# TIDA-010954-Control.net
KiCad netlist of a schematic drawn in Altium Designer
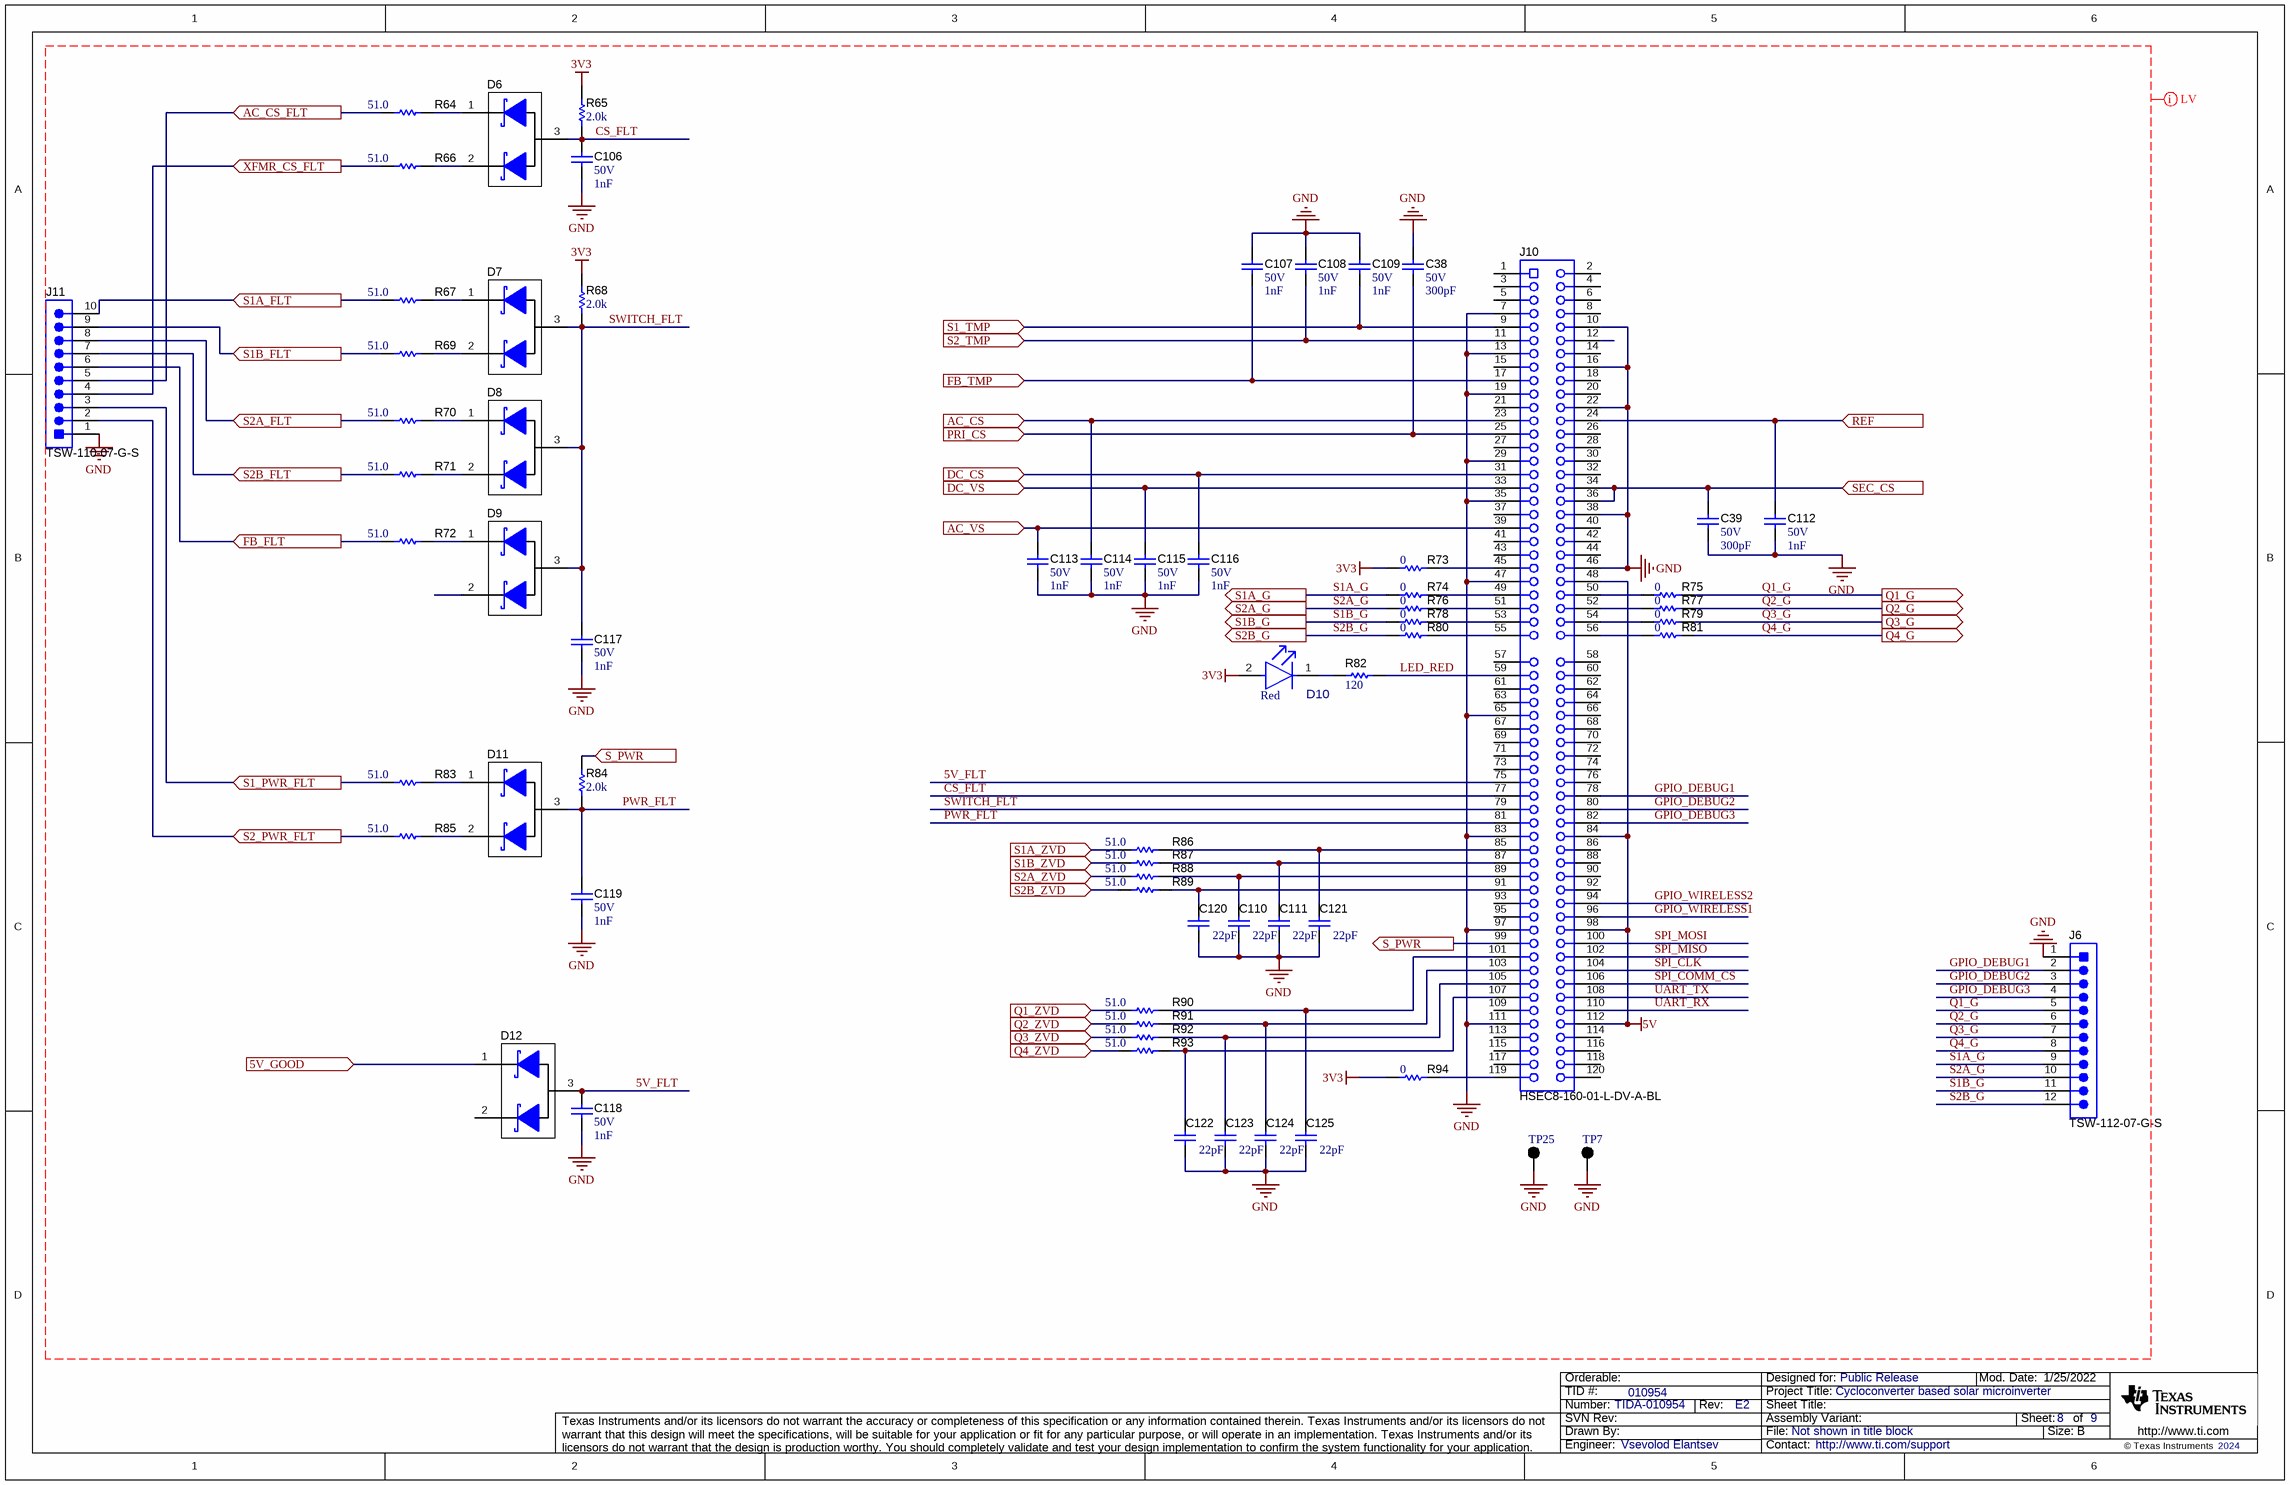
[diagram p0: TIDA-010954-Control.SchDoc]

(export (version "E")
  (design (tool "Eeschema 10.0.6"))
  (components
    (comp (ref "C38")
      (value "GRM1885C1H301JA01D")
      (footprint "0603")
      (description "CAP, CERM, 300 pF, 50 V, +/- 5%, C0G/NP0, 0603")
      (fields
        (field (name "MANUFACTURER") "MuRata")
        (field (name "VDC_V") "50V")
        (field (name "VALUEDISPLAYED") "300pF")
        (field (name "PUBLISHER") "Texas Instruments")
      )
      (libsource (lib "Altium Vault - TI") (part "Capacitor"))
    )
    (comp (ref "C39")
      (value "GRM1885C1H301JA01D")
      (footprint "0603")
      (description "CAP, CERM, 300 pF, 50 V, +/- 5%, C0G/NP0, 0603")
      (fields
        (field (name "MANUFACTURER") "MuRata")
        (field (name "VDC_V") "50V")
        (field (name "VALUEDISPLAYED") "300pF")
        (field (name "PUBLISHER") "Texas Instruments")
      )
      (libsource (lib "Altium Vault - TI") (part "Capacitor"))
    )
    (comp (ref "C106")
      (value "GRM1885C1H102JA01D")
      (footprint "0603")
      (description "CAP, CERM, 1000 pF, 50 V, +/- 5%, C0G/NP0, 0603")
      (fields
        (field (name "MANUFACTURER") "MuRata")
        (field (name "VDC_V") "50V")
        (field (name "VALUEDISPLAYED") "1nF")
        (field (name "PUBLISHER") "Texas Instruments")
      )
      (libsource (lib "Altium Vault - TI") (part "Capacitor"))
    )
    (comp (ref "C107")
      (value "GRM1885C1H102JA01D")
      (footprint "0603")
      (description "CAP, CERM, 1000 pF, 50 V, +/- 5%, C0G/NP0, 0603")
      (fields
        (field (name "MANUFACTURER") "MuRata")
        (field (name "VDC_V") "50V")
        (field (name "VALUEDISPLAYED") "1nF")
        (field (name "PUBLISHER") "Texas Instruments")
      )
      (libsource (lib "Altium Vault - TI") (part "Capacitor"))
    )
    (comp (ref "C108")
      (value "GRM1885C1H102JA01D")
      (footprint "0603")
      (description "CAP, CERM, 1000 pF, 50 V, +/- 5%, C0G/NP0, 0603")
      (fields
        (field (name "MANUFACTURER") "MuRata")
        (field (name "VDC_V") "50V")
        (field (name "VALUEDISPLAYED") "1nF")
        (field (name "PUBLISHER") "Texas Instruments")
      )
      (libsource (lib "Altium Vault - TI") (part "Capacitor"))
    )
    (comp (ref "C109")
      (value "GRM1885C1H102JA01D")
      (footprint "0603")
      (description "CAP, CERM, 1000 pF, 50 V, +/- 5%, C0G/NP0, 0603")
      (fields
        (field (name "MANUFACTURER") "MuRata")
        (field (name "VDC_V") "50V")
        (field (name "VALUEDISPLAYED") "1nF")
        (field (name "PUBLISHER") "Texas Instruments")
      )
      (libsource (lib "Altium Vault - TI") (part "Capacitor"))
    )
    (comp (ref "C110")
      (value "GRM1885C1H220JA01D")
      (footprint "0603")
      (description "CAP, CERM, 22 pF, 50 V, +/- 5%, C0G/NP0, 0603")
      (fields
        (field (name "MANUFACTURER") "MuRata")
        (field (name "VALUEDISPLAYED") "22pF")
        (field (name "PUBLISHER") "Texas Instruments")
      )
      (libsource (lib "Altium Vault - TI") (part "Capacitor"))
    )
    (comp (ref "C111")
      (value "GRM1885C1H220JA01D")
      (footprint "0603")
      (description "CAP, CERM, 22 pF, 50 V, +/- 5%, C0G/NP0, 0603")
      (fields
        (field (name "MANUFACTURER") "MuRata")
        (field (name "VALUEDISPLAYED") "22pF")
        (field (name "PUBLISHER") "Texas Instruments")
      )
      (libsource (lib "Altium Vault - TI") (part "Capacitor"))
    )
    (comp (ref "C112")
      (value "GRM1885C1H102JA01D")
      (footprint "0603")
      (description "CAP, CERM, 1000 pF, 50 V, +/- 5%, C0G/NP0, 0603")
      (fields
        (field (name "MANUFACTURER") "MuRata")
        (field (name "VDC_V") "50V")
        (field (name "VALUEDISPLAYED") "1nF")
        (field (name "PUBLISHER") "Texas Instruments")
      )
      (libsource (lib "Altium Vault - TI") (part "Capacitor"))
    )
    (comp (ref "C113")
      (value "GRM1885C1H102JA01D")
      (footprint "0603")
      (description "CAP, CERM, 1000 pF, 50 V, +/- 5%, C0G/NP0, 0603")
      (fields
        (field (name "MANUFACTURER") "MuRata")
        (field (name "VDC_V") "50V")
        (field (name "VALUEDISPLAYED") "1nF")
        (field (name "PUBLISHER") "Texas Instruments")
      )
      (libsource (lib "Altium Vault - TI") (part "Capacitor"))
    )
    (comp (ref "C114")
      (value "GRM1885C1H102JA01D")
      (footprint "0603")
      (description "CAP, CERM, 1000 pF, 50 V, +/- 5%, C0G/NP0, 0603")
      (fields
        (field (name "MANUFACTURER") "MuRata")
        (field (name "VDC_V") "50V")
        (field (name "VALUEDISPLAYED") "1nF")
        (field (name "PUBLISHER") "Texas Instruments")
      )
      (libsource (lib "Altium Vault - TI") (part "Capacitor"))
    )
    (comp (ref "C115")
      (value "GRM1885C1H102JA01D")
      (footprint "0603")
      (description "CAP, CERM, 1000 pF, 50 V, +/- 5%, C0G/NP0, 0603")
      (fields
        (field (name "MANUFACTURER") "MuRata")
        (field (name "VDC_V") "50V")
        (field (name "VALUEDISPLAYED") "1nF")
        (field (name "PUBLISHER") "Texas Instruments")
      )
      (libsource (lib "Altium Vault - TI") (part "Capacitor"))
    )
    (comp (ref "C116")
      (value "GRM1885C1H102JA01D")
      (footprint "0603")
      (description "CAP, CERM, 1000 pF, 50 V, +/- 5%, C0G/NP0, 0603")
      (fields
        (field (name "MANUFACTURER") "MuRata")
        (field (name "VDC_V") "50V")
        (field (name "VALUEDISPLAYED") "1nF")
        (field (name "PUBLISHER") "Texas Instruments")
      )
      (libsource (lib "Altium Vault - TI") (part "Capacitor"))
    )
    (comp (ref "C117")
      (value "GRM1885C1H102JA01D")
      (footprint "0603")
      (description "CAP, CERM, 1000 pF, 50 V, +/- 5%, C0G/NP0, 0603")
      (fields
        (field (name "MANUFACTURER") "MuRata")
        (field (name "VDC_V") "50V")
        (field (name "VALUEDISPLAYED") "1nF")
        (field (name "PUBLISHER") "Texas Instruments")
      )
      (libsource (lib "Altium Vault - TI") (part "Capacitor"))
    )
    (comp (ref "C118")
      (value "GRM1885C1H102JA01D")
      (footprint "0603")
      (description "CAP, CERM, 1000 pF, 50 V, +/- 5%, C0G/NP0, 0603")
      (fields
        (field (name "MANUFACTURER") "MuRata")
        (field (name "VDC_V") "50V")
        (field (name "VALUEDISPLAYED") "1nF")
        (field (name "PUBLISHER") "Texas Instruments")
      )
      (libsource (lib "Altium Vault - TI") (part "Capacitor"))
    )
    (comp (ref "C119")
      (value "GRM1885C1H102JA01D")
      (footprint "0603")
      (description "CAP, CERM, 1000 pF, 50 V, +/- 5%, C0G/NP0, 0603")
      (fields
        (field (name "MANUFACTURER") "MuRata")
        (field (name "VDC_V") "50V")
        (field (name "VALUEDISPLAYED") "1nF")
        (field (name "PUBLISHER") "Texas Instruments")
      )
      (libsource (lib "Altium Vault - TI") (part "Capacitor"))
    )
    (comp (ref "C120")
      (value "GRM1885C1H220JA01D")
      (footprint "0603")
      (description "CAP, CERM, 22 pF, 50 V, +/- 5%, C0G/NP0, 0603")
      (fields
        (field (name "MANUFACTURER") "MuRata")
        (field (name "VALUEDISPLAYED") "22pF")
        (field (name "PUBLISHER") "Texas Instruments")
      )
      (libsource (lib "Altium Vault - TI") (part "Capacitor"))
    )
    (comp (ref "C121")
      (value "GRM1885C1H220JA01D")
      (footprint "0603")
      (description "CAP, CERM, 22 pF, 50 V, +/- 5%, C0G/NP0, 0603")
      (fields
        (field (name "MANUFACTURER") "MuRata")
        (field (name "VALUEDISPLAYED") "22pF")
        (field (name "PUBLISHER") "Texas Instruments")
      )
      (libsource (lib "Altium Vault - TI") (part "Capacitor"))
    )
    (comp (ref "C122")
      (value "GRM1885C1H220JA01D")
      (footprint "0603")
      (description "CAP, CERM, 22 pF, 50 V, +/- 5%, C0G/NP0, 0603")
      (fields
        (field (name "MANUFACTURER") "MuRata")
        (field (name "VALUEDISPLAYED") "22pF")
        (field (name "PUBLISHER") "Texas Instruments")
      )
      (libsource (lib "Altium Vault - TI") (part "Capacitor"))
    )
    (comp (ref "C123")
      (value "GRM1885C1H220JA01D")
      (footprint "0603")
      (description "CAP, CERM, 22 pF, 50 V, +/- 5%, C0G/NP0, 0603")
      (fields
        (field (name "MANUFACTURER") "MuRata")
        (field (name "VALUEDISPLAYED") "22pF")
        (field (name "PUBLISHER") "Texas Instruments")
      )
      (libsource (lib "Altium Vault - TI") (part "Capacitor"))
    )
    (comp (ref "C124")
      (value "GRM1885C1H220JA01D")
      (footprint "0603")
      (description "CAP, CERM, 22 pF, 50 V, +/- 5%, C0G/NP0, 0603")
      (fields
        (field (name "MANUFACTURER") "MuRata")
        (field (name "VALUEDISPLAYED") "22pF")
        (field (name "PUBLISHER") "Texas Instruments")
      )
      (libsource (lib "Altium Vault - TI") (part "Capacitor"))
    )
    (comp (ref "C125")
      (value "GRM1885C1H220JA01D")
      (footprint "0603")
      (description "CAP, CERM, 22 pF, 50 V, +/- 5%, C0G/NP0, 0603")
      (fields
        (field (name "MANUFACTURER") "MuRata")
        (field (name "VALUEDISPLAYED") "22pF")
        (field (name "PUBLISHER") "Texas Instruments")
      )
      (libsource (lib "Altium Vault - TI") (part "Capacitor"))
    )
    (comp (ref "D6")
      (value "BAT54AWT-TP")
      (footprint "SOT-323")
      (description "Diode, Schottky, 30 V, 0.2 A, SOT-323")
      (fields (field (name "MANUFACTURER") "Micro Commercial Components"))
      (libsource (lib "Altium Vault - TI") (part "DIODE_SCHOTTKY_A3C1_A3C2"))
    )
    (comp (ref "D7")
      (value "BAT54AWT-TP")
      (footprint "SOT-323")
      (description "Diode, Schottky, 30 V, 0.2 A, SOT-323")
      (fields (field (name "MANUFACTURER") "Micro Commercial Components"))
      (libsource (lib "Altium Vault - TI") (part "DIODE_SCHOTTKY_A3C1_A3C2"))
    )
    (comp (ref "D8")
      (value "BAT54AWT-TP")
      (footprint "SOT-323")
      (description "Diode, Schottky, 30 V, 0.2 A, SOT-323")
      (fields (field (name "MANUFACTURER") "Micro Commercial Components"))
      (libsource (lib "Altium Vault - TI") (part "DIODE_SCHOTTKY_A3C1_A3C2"))
    )
    (comp (ref "D9")
      (value "BAT54AWT-TP")
      (footprint "SOT-323")
      (description "Diode, Schottky, 30 V, 0.2 A, SOT-323")
      (fields (field (name "MANUFACTURER") "Micro Commercial Components"))
      (libsource (lib "Altium Vault - TI") (part "DIODE_SCHOTTKY_A3C1_A3C2"))
    )
    (comp (ref "D10")
      (value "APG1608SURKC/T")
      (footprint "FP-APG1608SURKC_T_0603-MFG")
      (description "Red 630nm LED Indication - Discrete 2V 0603 (1608 Metric)")
      (fields
        (field (name "MANUFACTURER") "Kingbright")
        (field (name "MOUSER PART NUMBER") "604-APG1608SURKC/T")
        (field (name "COLOR") "Red")
      )
      (libsource (lib "Altium Vault - TI") (part "SYM-APG1608SURKC_T"))
    )
    (comp (ref "D11")
      (value "BAT54AWT-TP")
      (footprint "SOT-323")
      (description "Diode, Schottky, 30 V, 0.2 A, SOT-323")
      (fields (field (name "MANUFACTURER") "Micro Commercial Components"))
      (libsource (lib "Altium Vault - TI") (part "DIODE_SCHOTTKY_A3C1_A3C2"))
    )
    (comp (ref "D12")
      (value "BAT54AWT-TP")
      (footprint "SOT-323")
      (description "Diode, Schottky, 30 V, 0.2 A, SOT-323")
      (fields (field (name "MANUFACTURER") "Micro Commercial Components"))
      (libsource (lib "Altium Vault - TI") (part "DIODE_SCHOTTKY_A3C1_A3C2"))
    )
    (comp (ref "J6")
      (value "TSW-112-07-G-S")
      (footprint "TSW-112-07-G-S")
      (description "Header, 100mil, 12x1, Gold, TH")
      (fields (field (name "MANUFACTURER") "Samtec") (field (name "PUBLISHER") "Texas Instruments"))
      (libsource (lib "Altium Vault - TI") (part "Header_12x1"))
    )
    (comp (ref "J10")
      (value "HSEC8-160-01-L-DV-A-BL")
      (footprint "controlCARD-120HSEC")
      (description "C2000 controlCARD-120HSEC connector, SMT")
      (fields (field (name "MANUFACTURER") "Samtec"))
      (libsource (lib "Altium Vault - TI") (part "controlCARD-120HSEC"))
    )
    (comp (ref "J11")
      (value "TSW-110-07-G-S")
      (footprint "TSW-110-07-G-S")
      (description "Header, 100mil, 10x1, Gold, TH")
      (fields (field (name "MANUFACTURER") "Samtec") (field (name "PUBLISHER") "Texas Instruments"))
      (libsource (lib "Altium Vault - TI") (part "Header_10x1"))
    )
    (comp (ref "R64")
      (value "RC0603FR-0751RL")
      (footprint "0603")
      (description "RES, 51.0, 1%, 0.1 W, 0603")
      (fields (field (name "MANUFACTURER") "Yageo") (field (name "VALUEDISPLAYED") "51.0"))
      (libsource (lib "Altium Vault - TI") (part "Resistor"))
    )
    (comp (ref "R65")
      (value "RC0603JR-072KL")
      (footprint "0603")
      (description "RES, 2.0 k, 5%, 0.1 W, 0603")
      (fields (field (name "MANUFACTURER") "Yageo") (field (name "VALUEDISPLAYED") "2.0k"))
      (libsource (lib "Altium Vault - TI") (part "Resistor"))
    )
    (comp (ref "R66")
      (value "RC0603FR-0751RL")
      (footprint "0603")
      (description "RES, 51.0, 1%, 0.1 W, 0603")
      (fields (field (name "MANUFACTURER") "Yageo") (field (name "VALUEDISPLAYED") "51.0"))
      (libsource (lib "Altium Vault - TI") (part "Resistor"))
    )
    (comp (ref "R67")
      (value "RC0603FR-0751RL")
      (footprint "0603")
      (description "RES, 51.0, 1%, 0.1 W, 0603")
      (fields (field (name "MANUFACTURER") "Yageo") (field (name "VALUEDISPLAYED") "51.0"))
      (libsource (lib "Altium Vault - TI") (part "Resistor"))
    )
    (comp (ref "R68")
      (value "RC0603JR-072KL")
      (footprint "0603")
      (description "RES, 2.0 k, 5%, 0.1 W, 0603")
      (fields (field (name "MANUFACTURER") "Yageo") (field (name "VALUEDISPLAYED") "2.0k"))
      (libsource (lib "Altium Vault - TI") (part "Resistor"))
    )
    (comp (ref "R69")
      (value "RC0603FR-0751RL")
      (footprint "0603")
      (description "RES, 51.0, 1%, 0.1 W, 0603")
      (fields (field (name "MANUFACTURER") "Yageo") (field (name "VALUEDISPLAYED") "51.0"))
      (libsource (lib "Altium Vault - TI") (part "Resistor"))
    )
    (comp (ref "R70")
      (value "RC0603FR-0751RL")
      (footprint "0603")
      (description "RES, 51.0, 1%, 0.1 W, 0603")
      (fields (field (name "MANUFACTURER") "Yageo") (field (name "VALUEDISPLAYED") "51.0"))
      (libsource (lib "Altium Vault - TI") (part "Resistor"))
    )
    (comp (ref "R71")
      (value "RC0603FR-0751RL")
      (footprint "0603")
      (description "RES, 51.0, 1%, 0.1 W, 0603")
      (fields (field (name "MANUFACTURER") "Yageo") (field (name "VALUEDISPLAYED") "51.0"))
      (libsource (lib "Altium Vault - TI") (part "Resistor"))
    )
    (comp (ref "R72")
      (value "RC0603FR-0751RL")
      (footprint "0603")
      (description "RES, 51.0, 1%, 0.1 W, 0603")
      (fields (field (name "MANUFACTURER") "Yageo") (field (name "VALUEDISPLAYED") "51.0"))
      (libsource (lib "Altium Vault - TI") (part "Resistor"))
    )
    (comp (ref "R73")
      (value "RC0603JR-070RL")
      (footprint "0603")
      (description "RES, 0, 5%, 0.1 W, 0603")
      (fields (field (name "MANUFACTURER") "Yageo") (field (name "VALUEDISPLAYED") "0"))
      (libsource (lib "Altium Vault - TI") (part "Resistor"))
    )
    (comp (ref "R74")
      (value "RC0603JR-070RL")
      (footprint "0603")
      (description "RES, 0, 5%, 0.1 W, 0603")
      (fields (field (name "MANUFACTURER") "Yageo") (field (name "VALUEDISPLAYED") "0"))
      (libsource (lib "Altium Vault - TI") (part "Resistor"))
    )
    (comp (ref "R75")
      (value "RC0603JR-070RL")
      (footprint "0603")
      (description "RES, 0, 5%, 0.1 W, 0603")
      (fields (field (name "MANUFACTURER") "Yageo") (field (name "VALUEDISPLAYED") "0"))
      (libsource (lib "Altium Vault - TI") (part "Resistor"))
    )
    (comp (ref "R76")
      (value "RC0603JR-070RL")
      (footprint "0603")
      (description "RES, 0, 5%, 0.1 W, 0603")
      (fields (field (name "MANUFACTURER") "Yageo") (field (name "VALUEDISPLAYED") "0"))
      (libsource (lib "Altium Vault - TI") (part "Resistor"))
    )
    (comp (ref "R77")
      (value "RC0603JR-070RL")
      (footprint "0603")
      (description "RES, 0, 5%, 0.1 W, 0603")
      (fields (field (name "MANUFACTURER") "Yageo") (field (name "VALUEDISPLAYED") "0"))
      (libsource (lib "Altium Vault - TI") (part "Resistor"))
    )
    (comp (ref "R78")
      (value "RC0603JR-070RL")
      (footprint "0603")
      (description "RES, 0, 5%, 0.1 W, 0603")
      (fields (field (name "MANUFACTURER") "Yageo") (field (name "VALUEDISPLAYED") "0"))
      (libsource (lib "Altium Vault - TI") (part "Resistor"))
    )
    (comp (ref "R79")
      (value "RC0603JR-070RL")
      (footprint "0603")
      (description "RES, 0, 5%, 0.1 W, 0603")
      (fields (field (name "MANUFACTURER") "Yageo") (field (name "VALUEDISPLAYED") "0"))
      (libsource (lib "Altium Vault - TI") (part "Resistor"))
    )
    (comp (ref "R80")
      (value "RC0603JR-070RL")
      (footprint "0603")
      (description "RES, 0, 5%, 0.1 W, 0603")
      (fields (field (name "MANUFACTURER") "Yageo") (field (name "VALUEDISPLAYED") "0"))
      (libsource (lib "Altium Vault - TI") (part "Resistor"))
    )
    (comp (ref "R81")
      (value "RC0603JR-070RL")
      (footprint "0603")
      (description "RES, 0, 5%, 0.1 W, 0603")
      (fields (field (name "MANUFACTURER") "Yageo") (field (name "VALUEDISPLAYED") "0"))
      (libsource (lib "Altium Vault - TI") (part "Resistor"))
    )
    (comp (ref "R82")
      (value "RC0603FR-07120RL")
      (footprint "0603")
      (description "RES, 120, 1%, 0.1 W, 0603")
      (fields (field (name "MANUFACTURER") "Yageo") (field (name "VALUEDISPLAYED") "120"))
      (libsource (lib "Altium Vault - TI") (part "Resistor"))
    )
    (comp (ref "R83")
      (value "RC0603FR-0751RL")
      (footprint "0603")
      (description "RES, 51.0, 1%, 0.1 W, 0603")
      (fields (field (name "MANUFACTURER") "Yageo") (field (name "VALUEDISPLAYED") "51.0"))
      (libsource (lib "Altium Vault - TI") (part "Resistor"))
    )
    (comp (ref "R84")
      (value "RC0603JR-072KL")
      (footprint "0603")
      (description "RES, 2.0 k, 5%, 0.1 W, 0603")
      (fields (field (name "MANUFACTURER") "Yageo") (field (name "VALUEDISPLAYED") "2.0k"))
      (libsource (lib "Altium Vault - TI") (part "Resistor"))
    )
    (comp (ref "R85")
      (value "RC0603FR-0751RL")
      (footprint "0603")
      (description "RES, 51.0, 1%, 0.1 W, 0603")
      (fields (field (name "MANUFACTURER") "Yageo") (field (name "VALUEDISPLAYED") "51.0"))
      (libsource (lib "Altium Vault - TI") (part "Resistor"))
    )
    (comp (ref "R86")
      (value "RC0603FR-0751RL")
      (footprint "0603")
      (description "RES, 51.0, 1%, 0.1 W, 0603")
      (fields (field (name "MANUFACTURER") "Yageo") (field (name "VALUEDISPLAYED") "51.0"))
      (libsource (lib "Altium Vault - TI") (part "Resistor"))
    )
    (comp (ref "R87")
      (value "RC0603FR-0751RL")
      (footprint "0603")
      (description "RES, 51.0, 1%, 0.1 W, 0603")
      (fields (field (name "MANUFACTURER") "Yageo") (field (name "VALUEDISPLAYED") "51.0"))
      (libsource (lib "Altium Vault - TI") (part "Resistor"))
    )
    (comp (ref "R88")
      (value "RC0603FR-0751RL")
      (footprint "0603")
      (description "RES, 51.0, 1%, 0.1 W, 0603")
      (fields (field (name "MANUFACTURER") "Yageo") (field (name "VALUEDISPLAYED") "51.0"))
      (libsource (lib "Altium Vault - TI") (part "Resistor"))
    )
    (comp (ref "R89")
      (value "RC0603FR-0751RL")
      (footprint "0603")
      (description "RES, 51.0, 1%, 0.1 W, 0603")
      (fields (field (name "MANUFACTURER") "Yageo") (field (name "VALUEDISPLAYED") "51.0"))
      (libsource (lib "Altium Vault - TI") (part "Resistor"))
    )
    (comp (ref "R90")
      (value "RC0603FR-0751RL")
      (footprint "0603")
      (description "RES, 51.0, 1%, 0.1 W, 0603")
      (fields (field (name "MANUFACTURER") "Yageo") (field (name "VALUEDISPLAYED") "51.0"))
      (libsource (lib "Altium Vault - TI") (part "Resistor"))
    )
    (comp (ref "R91")
      (value "RC0603FR-0751RL")
      (footprint "0603")
      (description "RES, 51.0, 1%, 0.1 W, 0603")
      (fields (field (name "MANUFACTURER") "Yageo") (field (name "VALUEDISPLAYED") "51.0"))
      (libsource (lib "Altium Vault - TI") (part "Resistor"))
    )
    (comp (ref "R92")
      (value "RC0603FR-0751RL")
      (footprint "0603")
      (description "RES, 51.0, 1%, 0.1 W, 0603")
      (fields (field (name "MANUFACTURER") "Yageo") (field (name "VALUEDISPLAYED") "51.0"))
      (libsource (lib "Altium Vault - TI") (part "Resistor"))
    )
    (comp (ref "R93")
      (value "RC0603FR-0751RL")
      (footprint "0603")
      (description "RES, 51.0, 1%, 0.1 W, 0603")
      (fields (field (name "MANUFACTURER") "Yageo") (field (name "VALUEDISPLAYED") "51.0"))
      (libsource (lib "Altium Vault - TI") (part "Resistor"))
    )
    (comp (ref "R94")
      (value "RC0603JR-070RL")
      (footprint "0603")
      (description "RES, 0, 5%, 0.1 W, 0603")
      (fields (field (name "MANUFACTURER") "Yageo") (field (name "VALUEDISPLAYED") "0"))
      (libsource (lib "Altium Vault - TI") (part "Resistor"))
    )
    (comp (ref "TP7")
      (value "5011")
      (footprint "Keystone5011")
      (description "Test Point, Multipurpose, Black, TH")
      (fields
        (field (name "MANUFACTURER") "Keystone Electronics")
        (field (name "PUBLISHER") "Texas Instruments")
      )
      (libsource (lib "Altium Vault - TI") (part "5011"))
    )
    (comp (ref "TP25")
      (value "5011")
      (footprint "Keystone5011")
      (description "Test Point, Multipurpose, Black, TH")
      (fields
        (field (name "MANUFACTURER") "Keystone Electronics")
        (field (name "PUBLISHER") "Texas Instruments")
      )
      (libsource (lib "Altium Vault - TI") (part "5011"))
    )
  )
  (nets
    (net (code "1") (name "/5V_FLT") (class "Default")
      (node (ref "C118") (pin "1") (pinfunction "1_1") (pintype "passive"))
      (node (ref "D12") (pin "3") (pinfunction "A_3") (pintype "passive"))
      (node (ref "J10") (pin "75") (pinfunction "75_75") (pintype "passive"))
    )
    (net (code "2") (name "/5V_GOOD") (class "Default")
      (node (ref "D12") (pin "1") (pinfunction "A_1") (pintype "passive"))
    )
    (net (code "3") (name "/AC_CS") (class "Default")
      (node (ref "C114") (pin "1") (pinfunction "1_1") (pintype "passive"))
      (node (ref "J10") (pin "23") (pinfunction "23_23") (pintype "passive"))
    )
    (net (code "4") (name "/AC_CS_FLT") (class "Default")
      (node (ref "J11") (pin "5") (pinfunction "5_5") (pintype "passive"))
      (node (ref "R64") (pin "1") (pinfunction "1_1") (pintype "passive"))
    )
    (net (code "5") (name "/AC_VS") (class "Default")
      (node (ref "C113") (pin "1") (pinfunction "1_1") (pintype "passive"))
      (node (ref "J10") (pin "39") (pinfunction "39_39") (pintype "passive"))
    )
    (net (code "6") (name "/CS_FLT") (class "Default")
      (node (ref "C106") (pin "1") (pinfunction "1_1") (pintype "passive"))
      (node (ref "D6") (pin "3") (pinfunction "A_3") (pintype "passive"))
      (node (ref "J10") (pin "77") (pinfunction "77_77") (pintype "passive"))
      (node (ref "R65") (pin "1") (pinfunction "1_1") (pintype "passive"))
    )
    (net (code "7") (name "/DC_CS") (class "Default")
      (node (ref "C116") (pin "1") (pinfunction "1_1") (pintype "passive"))
      (node (ref "J10") (pin "31") (pinfunction "31_31") (pintype "passive"))
    )
    (net (code "8") (name "/DC_VS") (class "Default")
      (node (ref "C115") (pin "1") (pinfunction "1_1") (pintype "passive"))
      (node (ref "J10") (pin "33") (pinfunction "33_33") (pintype "passive"))
    )
    (net (code "9") (name "/FB_FLT") (class "Default")
      (node (ref "J11") (pin "6") (pinfunction "6_6") (pintype "passive"))
      (node (ref "R72") (pin "1") (pinfunction "1_1") (pintype "passive"))
    )
    (net (code "10") (name "/FB_TMP") (class "Default")
      (node (ref "C107") (pin "2") (pinfunction "2_2") (pintype "passive"))
      (node (ref "J10") (pin "17") (pinfunction "17_17") (pintype "passive"))
    )
    (net (code "11") (name "/GPIO_DEBUG1") (class "Default")
      (node (ref "J10") (pin "78") (pinfunction "78_78") (pintype "passive"))
      (node (ref "J6") (pin "2") (pinfunction "2_2") (pintype "passive"))
    )
    (net (code "12") (name "/GPIO_DEBUG2") (class "Default")
      (node (ref "J10") (pin "80") (pinfunction "80_80") (pintype "passive"))
      (node (ref "J6") (pin "3") (pinfunction "3_3") (pintype "passive"))
    )
    (net (code "13") (name "/GPIO_DEBUG3") (class "Default")
      (node (ref "J10") (pin "82") (pinfunction "82_82") (pintype "passive"))
      (node (ref "J6") (pin "4") (pinfunction "4_4") (pintype "passive"))
    )
    (net (code "14") (name "/GPIO_WIRELESS1") (class "Default")
      (node (ref "J10") (pin "96") (pinfunction "96_96") (pintype "passive"))
    )
    (net (code "15") (name "/GPIO_WIRELESS2") (class "Default")
      (node (ref "J10") (pin "94") (pinfunction "94_94") (pintype "passive"))
    )
    (net (code "16") (name "/LED_RED") (class "Default")
      (node (ref "J10") (pin "59") (pinfunction "59_59") (pintype "passive"))
      (node (ref "R82") (pin "2") (pinfunction "2_2") (pintype "passive"))
    )
    (net (code "17") (name "/PRI_CS") (class "Default")
      (node (ref "C38") (pin "1") (pinfunction "1_1") (pintype "passive"))
      (node (ref "J10") (pin "25") (pinfunction "25_25") (pintype "passive"))
    )
    (net (code "18") (name "/PWR_FLT") (class "Default")
      (node (ref "C119") (pin "1") (pinfunction "1_1") (pintype "passive"))
      (node (ref "D11") (pin "3") (pinfunction "A_3") (pintype "passive"))
      (node (ref "J10") (pin "81") (pinfunction "81_81") (pintype "passive"))
      (node (ref "R84") (pin "1") (pinfunction "1_1") (pintype "passive"))
    )
    (net (code "19") (name "/Q1_G") (class "Default")
      (node (ref "J6") (pin "5") (pinfunction "5_5") (pintype "passive"))
      (node (ref "R75") (pin "2") (pinfunction "2_2") (pintype "passive"))
    )
    (net (code "20") (name "/Q1_ZVD") (class "Default")
      (node (ref "R90") (pin "1") (pinfunction "1_1") (pintype "passive"))
    )
    (net (code "21") (name "/Q2_G") (class "Default")
      (node (ref "J6") (pin "6") (pinfunction "6_6") (pintype "passive"))
      (node (ref "R77") (pin "2") (pinfunction "2_2") (pintype "passive"))
    )
    (net (code "22") (name "/Q2_ZVD") (class "Default")
      (node (ref "R91") (pin "1") (pinfunction "1_1") (pintype "passive"))
    )
    (net (code "23") (name "/Q3_G") (class "Default")
      (node (ref "J6") (pin "7") (pinfunction "7_7") (pintype "passive"))
      (node (ref "R79") (pin "2") (pinfunction "2_2") (pintype "passive"))
    )
    (net (code "24") (name "/Q3_ZVD") (class "Default")
      (node (ref "R92") (pin "1") (pinfunction "1_1") (pintype "passive"))
    )
    (net (code "25") (name "/Q4_G") (class "Default")
      (node (ref "J6") (pin "8") (pinfunction "8_8") (pintype "passive"))
      (node (ref "R81") (pin "2") (pinfunction "2_2") (pintype "passive"))
    )
    (net (code "26") (name "/Q4_ZVD") (class "Default")
      (node (ref "R93") (pin "1") (pinfunction "1_1") (pintype "passive"))
    )
    (net (code "27") (name "/REF") (class "Default")
      (node (ref "C112") (pin "1") (pinfunction "1_1") (pintype "passive"))
      (node (ref "J10") (pin "24") (pinfunction "24_24") (pintype "passive"))
    )
    (net (code "28") (name "/S1A_FLT") (class "Default")
      (node (ref "J11") (pin "10") (pinfunction "10_10") (pintype "passive"))
      (node (ref "R67") (pin "1") (pinfunction "1_1") (pintype "passive"))
    )
    (net (code "29") (name "/S1A_G") (class "Default")
      (node (ref "J6") (pin "9") (pinfunction "9_9") (pintype "passive"))
      (node (ref "R74") (pin "1") (pinfunction "1_1") (pintype "passive"))
    )
    (net (code "30") (name "/S1A_ZVD") (class "Default")
      (node (ref "R86") (pin "1") (pinfunction "1_1") (pintype "passive"))
    )
    (net (code "31") (name "/S1B_FLT") (class "Default")
      (node (ref "J11") (pin "9") (pinfunction "9_9") (pintype "passive"))
      (node (ref "R69") (pin "1") (pinfunction "1_1") (pintype "passive"))
    )
    (net (code "32") (name "/S1B_G") (class "Default")
      (node (ref "J6") (pin "11") (pinfunction "11_11") (pintype "passive"))
      (node (ref "R78") (pin "1") (pinfunction "1_1") (pintype "passive"))
    )
    (net (code "33") (name "/S1B_ZVD") (class "Default")
      (node (ref "R87") (pin "1") (pinfunction "1_1") (pintype "passive"))
    )
    (net (code "34") (name "/S1_PWR_FLT") (class "Default")
      (node (ref "J11") (pin "3") (pinfunction "3_3") (pintype "passive"))
      (node (ref "R83") (pin "1") (pinfunction "1_1") (pintype "passive"))
    )
    (net (code "35") (name "/S1_TMP") (class "Default")
      (node (ref "C109") (pin "2") (pinfunction "2_2") (pintype "passive"))
      (node (ref "J10") (pin "9") (pinfunction "9_9") (pintype "passive"))
    )
    (net (code "36") (name "/S2A_FLT") (class "Default")
      (node (ref "J11") (pin "8") (pinfunction "8_8") (pintype "passive"))
      (node (ref "R70") (pin "1") (pinfunction "1_1") (pintype "passive"))
    )
    (net (code "37") (name "/S2A_G") (class "Default")
      (node (ref "J6") (pin "10") (pinfunction "10_10") (pintype "passive"))
      (node (ref "R76") (pin "1") (pinfunction "1_1") (pintype "passive"))
    )
    (net (code "38") (name "/S2A_ZVD") (class "Default")
      (node (ref "R88") (pin "1") (pinfunction "1_1") (pintype "passive"))
    )
    (net (code "39") (name "/S2B_FLT") (class "Default")
      (node (ref "J11") (pin "7") (pinfunction "7_7") (pintype "passive"))
      (node (ref "R71") (pin "1") (pinfunction "1_1") (pintype "passive"))
    )
    (net (code "40") (name "/S2B_G") (class "Default")
      (node (ref "J6") (pin "12") (pinfunction "12_12") (pintype "passive"))
      (node (ref "R80") (pin "1") (pinfunction "1_1") (pintype "passive"))
    )
    (net (code "41") (name "/S2B_ZVD") (class "Default")
      (node (ref "R89") (pin "1") (pinfunction "1_1") (pintype "passive"))
    )
    (net (code "42") (name "/S2_PWR_FLT") (class "Default")
      (node (ref "J11") (pin "2") (pinfunction "2_2") (pintype "passive"))
      (node (ref "R85") (pin "1") (pinfunction "1_1") (pintype "passive"))
    )
    (net (code "43") (name "/S2_TMP") (class "Default")
      (node (ref "C108") (pin "2") (pinfunction "2_2") (pintype "passive"))
      (node (ref "J10") (pin "11") (pinfunction "11_11") (pintype "passive"))
    )
    (net (code "44") (name "/SEC_CS") (class "Default")
      (node (ref "C39") (pin "1") (pinfunction "1_1") (pintype "passive"))
      (node (ref "J10") (pin "34") (pinfunction "34_34") (pintype "passive"))
      (node (ref "J10") (pin "36") (pinfunction "36_36") (pintype "passive"))
    )
    (net (code "45") (name "/SPI_CLK") (class "Default")
      (node (ref "J10") (pin "104") (pinfunction "104_104") (pintype "passive"))
    )
    (net (code "46") (name "/SPI_COMM_CS") (class "Default")
      (node (ref "J10") (pin "106") (pinfunction "106_106") (pintype "passive"))
    )
    (net (code "47") (name "/SPI_MISO") (class "Default")
      (node (ref "J10") (pin "102") (pinfunction "102_102") (pintype "passive"))
    )
    (net (code "48") (name "/SPI_MOSI") (class "Default")
      (node (ref "J10") (pin "100") (pinfunction "100_100") (pintype "passive"))
    )
    (net (code "49") (name "/SWITCH_FLT") (class "Default")
      (node (ref "C117") (pin "1") (pinfunction "1_1") (pintype "passive"))
      (node (ref "D7") (pin "3") (pinfunction "A_3") (pintype "passive"))
      (node (ref "D8") (pin "3") (pinfunction "A_3") (pintype "passive"))
      (node (ref "D9") (pin "3") (pinfunction "A_3") (pintype "passive"))
      (node (ref "J10") (pin "79") (pinfunction "79_79") (pintype "passive"))
      (node (ref "R68") (pin "1") (pinfunction "1_1") (pintype "passive"))
    )
    (net (code "50") (name "/S_PWR") (class "Default")
      (node (ref "J10") (pin "99") (pinfunction "99_99") (pintype "passive"))
      (node (ref "R84") (pin "2") (pinfunction "2_2") (pintype "passive"))
    )
    (net (code "51") (name "/UART_RX") (class "Default")
      (node (ref "J10") (pin "110") (pinfunction "110_110") (pintype "passive"))
    )
    (net (code "52") (name "/UART_TX") (class "Default")
      (node (ref "J10") (pin "108") (pinfunction "108_108") (pintype "passive"))
    )
    (net (code "53") (name "/XFMR_CS_FLT") (class "Default")
      (node (ref "J11") (pin "4") (pinfunction "4_4") (pintype "passive"))
      (node (ref "R66") (pin "1") (pinfunction "1_1") (pintype "passive"))
    )
    (net (code "54") (name "3V3") (class "Default")
      (node (ref "D10") (pin "2") (pinfunction "ANODE_2") (pintype "passive"))
      (node (ref "R65") (pin "2") (pinfunction "2_2") (pintype "passive"))
      (node (ref "R68") (pin "2") (pinfunction "2_2") (pintype "passive"))
      (node (ref "R73") (pin "1") (pinfunction "1_1") (pintype "passive"))
      (node (ref "R94") (pin "1") (pinfunction "1_1") (pintype "passive"))
    )
    (net (code "55") (name "5V") (class "Default")
      (node (ref "J10") (pin "112") (pinfunction "112_112") (pintype "passive"))
      (node (ref "J10") (pin "48") (pinfunction "48_48") (pintype "passive"))
      (node (ref "J10") (pin "84") (pinfunction "84_84") (pintype "passive"))
      (node (ref "J10") (pin "98") (pinfunction "98_98") (pintype "passive"))
    )
    (net (code "56") (name "GND") (class "Default")
      (node (ref "C106") (pin "2") (pinfunction "2_2") (pintype "passive"))
      (node (ref "C107") (pin "1") (pinfunction "1_1") (pintype "passive"))
      (node (ref "C108") (pin "1") (pinfunction "1_1") (pintype "passive"))
      (node (ref "C109") (pin "1") (pinfunction "1_1") (pintype "passive"))
      (node (ref "C110") (pin "2") (pinfunction "2_2") (pintype "passive"))
      (node (ref "C111") (pin "2") (pinfunction "2_2") (pintype "passive"))
      (node (ref "C112") (pin "2") (pinfunction "2_2") (pintype "passive"))
      (node (ref "C113") (pin "2") (pinfunction "2_2") (pintype "passive"))
      (node (ref "C114") (pin "2") (pinfunction "2_2") (pintype "passive"))
      (node (ref "C115") (pin "2") (pinfunction "2_2") (pintype "passive"))
      (node (ref "C116") (pin "2") (pinfunction "2_2") (pintype "passive"))
      (node (ref "C117") (pin "2") (pinfunction "2_2") (pintype "passive"))
      (node (ref "C118") (pin "2") (pinfunction "2_2") (pintype "passive"))
      (node (ref "C119") (pin "2") (pinfunction "2_2") (pintype "passive"))
      (node (ref "C120") (pin "2") (pinfunction "2_2") (pintype "passive"))
      (node (ref "C121") (pin "2") (pinfunction "2_2") (pintype "passive"))
      (node (ref "C122") (pin "2") (pinfunction "2_2") (pintype "passive"))
      (node (ref "C123") (pin "2") (pinfunction "2_2") (pintype "passive"))
      (node (ref "C124") (pin "2") (pinfunction "2_2") (pintype "passive"))
      (node (ref "C125") (pin "2") (pinfunction "2_2") (pintype "passive"))
      (node (ref "C38") (pin "2") (pinfunction "2_2") (pintype "passive"))
      (node (ref "C39") (pin "2") (pinfunction "2_2") (pintype "passive"))
      (node (ref "J10") (pin "10") (pinfunction "10_10") (pintype "passive"))
      (node (ref "J10") (pin "111") (pinfunction "111_111") (pintype "passive"))
      (node (ref "J10") (pin "13") (pinfunction "13_13") (pintype "passive"))
      (node (ref "J10") (pin "16") (pinfunction "16_16") (pintype "passive"))
      (node (ref "J10") (pin "19") (pinfunction "19_19") (pintype "passive"))
      (node (ref "J10") (pin "22") (pinfunction "22_22") (pintype "passive"))
      (node (ref "J10") (pin "29") (pinfunction "29_29") (pintype "passive"))
      (node (ref "J10") (pin "35") (pinfunction "35_35") (pintype "passive"))
      (node (ref "J10") (pin "38") (pinfunction "38_38") (pintype "passive"))
      (node (ref "J10") (pin "46") (pinfunction "46_46") (pintype "passive"))
      (node (ref "J10") (pin "47") (pinfunction "47_47") (pintype "passive"))
      (node (ref "J10") (pin "65") (pinfunction "65_65") (pintype "passive"))
      (node (ref "J10") (pin "7") (pinfunction "7_7") (pintype "passive"))
      (node (ref "J10") (pin "83") (pinfunction "83_83") (pintype "passive"))
      (node (ref "J10") (pin "97") (pinfunction "97_97") (pintype "passive"))
      (node (ref "J11") (pin "1") (pinfunction "1_1") (pintype "passive"))
      (node (ref "J6") (pin "1") (pinfunction "1_1") (pintype "passive"))
      (node (ref "TP25") (pin "1") (pintype "passive"))
      (node (ref "TP7") (pin "1") (pintype "passive"))
    )
    (net (code "57") (name "Net-(C110-Pad1)") (class "Default")
      (node (ref "C110") (pin "1") (pinfunction "1_1") (pintype "passive"))
      (node (ref "J10") (pin "89") (pinfunction "89_89") (pintype "passive"))
      (node (ref "R88") (pin "2") (pinfunction "2_2") (pintype "passive"))
    )
    (net (code "58") (name "Net-(C111-Pad1)") (class "Default")
      (node (ref "C111") (pin "1") (pinfunction "1_1") (pintype "passive"))
      (node (ref "J10") (pin "87") (pinfunction "87_87") (pintype "passive"))
      (node (ref "R87") (pin "2") (pinfunction "2_2") (pintype "passive"))
    )
    (net (code "59") (name "Net-(C120-Pad1)") (class "Default")
      (node (ref "C120") (pin "1") (pinfunction "1_1") (pintype "passive"))
      (node (ref "J10") (pin "91") (pinfunction "91_91") (pintype "passive"))
      (node (ref "R89") (pin "2") (pinfunction "2_2") (pintype "passive"))
    )
    (net (code "60") (name "Net-(C121-Pad1)") (class "Default")
      (node (ref "C121") (pin "1") (pinfunction "1_1") (pintype "passive"))
      (node (ref "J10") (pin "85") (pinfunction "85_85") (pintype "passive"))
      (node (ref "R86") (pin "2") (pinfunction "2_2") (pintype "passive"))
    )
    (net (code "61") (name "Net-(C122-Pad1)") (class "Default")
      (node (ref "C122") (pin "1") (pinfunction "1_1") (pintype "passive"))
      (node (ref "J10") (pin "107") (pinfunction "107_107") (pintype "passive"))
      (node (ref "R93") (pin "2") (pinfunction "2_2") (pintype "passive"))
    )
    (net (code "62") (name "Net-(C123-Pad1)") (class "Default")
      (node (ref "C123") (pin "1") (pinfunction "1_1") (pintype "passive"))
      (node (ref "J10") (pin "105") (pinfunction "105_105") (pintype "passive"))
      (node (ref "R92") (pin "2") (pinfunction "2_2") (pintype "passive"))
    )
    (net (code "63") (name "Net-(C124-Pad1)") (class "Default")
      (node (ref "C124") (pin "1") (pinfunction "1_1") (pintype "passive"))
      (node (ref "J10") (pin "103") (pinfunction "103_103") (pintype "passive"))
      (node (ref "R91") (pin "2") (pinfunction "2_2") (pintype "passive"))
    )
    (net (code "64") (name "Net-(C125-Pad1)") (class "Default")
      (node (ref "C125") (pin "1") (pinfunction "1_1") (pintype "passive"))
      (node (ref "J10") (pin "101") (pinfunction "101_101") (pintype "passive"))
      (node (ref "R90") (pin "2") (pinfunction "2_2") (pintype "passive"))
    )
    (net (code "65") (name "Net-(D6-A-Pad1)") (class "Default")
      (node (ref "D6") (pin "1") (pinfunction "A_1") (pintype "passive"))
      (node (ref "R64") (pin "2") (pinfunction "2_2") (pintype "passive"))
    )
    (net (code "66") (name "Net-(D6-K)") (class "Default")
      (node (ref "D6") (pin "2") (pinfunction "K_2") (pintype "passive"))
      (node (ref "R66") (pin "2") (pinfunction "2_2") (pintype "passive"))
    )
    (net (code "67") (name "Net-(D7-A-Pad1)") (class "Default")
      (node (ref "D7") (pin "1") (pinfunction "A_1") (pintype "passive"))
      (node (ref "R67") (pin "2") (pinfunction "2_2") (pintype "passive"))
    )
    (net (code "68") (name "Net-(D7-K)") (class "Default")
      (node (ref "D7") (pin "2") (pinfunction "K_2") (pintype "passive"))
      (node (ref "R69") (pin "2") (pinfunction "2_2") (pintype "passive"))
    )
    (net (code "69") (name "Net-(D8-A-Pad1)") (class "Default")
      (node (ref "D8") (pin "1") (pinfunction "A_1") (pintype "passive"))
      (node (ref "R70") (pin "2") (pinfunction "2_2") (pintype "passive"))
    )
    (net (code "70") (name "Net-(D8-K)") (class "Default")
      (node (ref "D8") (pin "2") (pinfunction "K_2") (pintype "passive"))
      (node (ref "R71") (pin "2") (pinfunction "2_2") (pintype "passive"))
    )
    (net (code "71") (name "Net-(D9-A-Pad1)") (class "Default")
      (node (ref "D9") (pin "1") (pinfunction "A_1") (pintype "passive"))
      (node (ref "R72") (pin "2") (pinfunction "2_2") (pintype "passive"))
    )
    (net (code "72") (name "Net-(D10-CATHODE)") (class "Default")
      (node (ref "D10") (pin "1") (pinfunction "CATHODE_1") (pintype "passive"))
      (node (ref "R82") (pin "1") (pinfunction "1_1") (pintype "passive"))
    )
    (net (code "73") (name "Net-(D11-A-Pad1)") (class "Default")
      (node (ref "D11") (pin "1") (pinfunction "A_1") (pintype "passive"))
      (node (ref "R83") (pin "2") (pinfunction "2_2") (pintype "passive"))
    )
    (net (code "74") (name "Net-(D11-K)") (class "Default")
      (node (ref "D11") (pin "2") (pinfunction "K_2") (pintype "passive"))
      (node (ref "R85") (pin "2") (pinfunction "2_2") (pintype "passive"))
    )
    (net (code "75") (name "Net-(J10-Pad45)") (class "Default")
      (node (ref "J10") (pin "45") (pinfunction "45_45") (pintype "passive"))
      (node (ref "R73") (pin "2") (pinfunction "2_2") (pintype "passive"))
    )
    (net (code "76") (name "Net-(J10-Pad49)") (class "Default")
      (node (ref "J10") (pin "49") (pinfunction "49_49") (pintype "passive"))
      (node (ref "R74") (pin "2") (pinfunction "2_2") (pintype "passive"))
    )
    (net (code "77") (name "Net-(J10-Pad50)") (class "Default")
      (node (ref "J10") (pin "50") (pinfunction "50_50") (pintype "passive"))
      (node (ref "R75") (pin "1") (pinfunction "1_1") (pintype "passive"))
    )
    (net (code "78") (name "Net-(J10-Pad51)") (class "Default")
      (node (ref "J10") (pin "51") (pinfunction "51_51") (pintype "passive"))
      (node (ref "R76") (pin "2") (pinfunction "2_2") (pintype "passive"))
    )
    (net (code "79") (name "Net-(J10-Pad52)") (class "Default")
      (node (ref "J10") (pin "52") (pinfunction "52_52") (pintype "passive"))
      (node (ref "R77") (pin "1") (pinfunction "1_1") (pintype "passive"))
    )
    (net (code "80") (name "Net-(J10-Pad53)") (class "Default")
      (node (ref "J10") (pin "53") (pinfunction "53_53") (pintype "passive"))
      (node (ref "R78") (pin "2") (pinfunction "2_2") (pintype "passive"))
    )
    (net (code "81") (name "Net-(J10-Pad54)") (class "Default")
      (node (ref "J10") (pin "54") (pinfunction "54_54") (pintype "passive"))
      (node (ref "R79") (pin "1") (pinfunction "1_1") (pintype "passive"))
    )
    (net (code "82") (name "Net-(J10-Pad55)") (class "Default")
      (node (ref "J10") (pin "55") (pinfunction "55_55") (pintype "passive"))
      (node (ref "R80") (pin "2") (pinfunction "2_2") (pintype "passive"))
    )
    (net (code "83") (name "Net-(J10-Pad56)") (class "Default")
      (node (ref "J10") (pin "56") (pinfunction "56_56") (pintype "passive"))
      (node (ref "R81") (pin "1") (pinfunction "1_1") (pintype "passive"))
    )
    (net (code "84") (name "Net-(J10-Pad119)") (class "Default")
      (node (ref "J10") (pin "119") (pinfunction "119_119") (pintype "passive"))
      (node (ref "R94") (pin "2") (pinfunction "2_2") (pintype "passive"))
    )
    (net (code "85") (name "unconnected-(D9-K-Pad2)") (class "Default")
      (node (ref "D9") (pin "2") (pinfunction "K_2") (pintype "passive"))
    )
    (net (code "86") (name "unconnected-(D12-K-Pad2)") (class "Default")
      (node (ref "D12") (pin "2") (pinfunction "K_2") (pintype "passive"))
    )
    (net (code "87") (name "unconnected-(J10-Pad1)") (class "Default")
      (node (ref "J10") (pin "1") (pinfunction "1_1") (pintype "passive"))
    )
    (net (code "88") (name "unconnected-(J10-Pad2)") (class "Default")
      (node (ref "J10") (pin "2") (pinfunction "2_2") (pintype "passive"))
    )
    (net (code "89") (name "unconnected-(J10-Pad3)") (class "Default")
      (node (ref "J10") (pin "3") (pinfunction "3_3") (pintype "passive"))
    )
    (net (code "90") (name "unconnected-(J10-Pad4)") (class "Default")
      (node (ref "J10") (pin "4") (pinfunction "4_4") (pintype "passive"))
    )
    (net (code "91") (name "unconnected-(J10-Pad5)") (class "Default")
      (node (ref "J10") (pin "5") (pinfunction "5_5") (pintype "passive"))
    )
    (net (code "92") (name "unconnected-(J10-Pad6)") (class "Default")
      (node (ref "J10") (pin "6") (pinfunction "6_6") (pintype "passive"))
    )
    (net (code "93") (name "unconnected-(J10-Pad8)") (class "Default")
      (node (ref "J10") (pin "8") (pinfunction "8_8") (pintype "passive"))
    )
    (net (code "94") (name "unconnected-(J10-Pad12)") (class "Default")
      (node (ref "J10") (pin "12") (pinfunction "12_12") (pintype "passive"))
    )
    (net (code "95") (name "unconnected-(J10-Pad14)") (class "Default")
      (node (ref "J10") (pin "14") (pinfunction "14_14") (pintype "passive"))
    )
    (net (code "96") (name "unconnected-(J10-Pad15)") (class "Default")
      (node (ref "J10") (pin "15") (pinfunction "15_15") (pintype "passive"))
    )
    (net (code "97") (name "unconnected-(J10-Pad18)") (class "Default")
      (node (ref "J10") (pin "18") (pinfunction "18_18") (pintype "passive"))
    )
    (net (code "98") (name "unconnected-(J10-Pad20)") (class "Default")
      (node (ref "J10") (pin "20") (pinfunction "20_20") (pintype "passive"))
    )
    (net (code "99") (name "unconnected-(J10-Pad21)") (class "Default")
      (node (ref "J10") (pin "21") (pinfunction "21_21") (pintype "passive"))
    )
    (net (code "100") (name "unconnected-(J10-Pad26)") (class "Default")
      (node (ref "J10") (pin "26") (pinfunction "26_26") (pintype "passive"))
    )
    (net (code "101") (name "unconnected-(J10-Pad27)") (class "Default")
      (node (ref "J10") (pin "27") (pinfunction "27_27") (pintype "passive"))
    )
    (net (code "102") (name "unconnected-(J10-Pad28)") (class "Default")
      (node (ref "J10") (pin "28") (pinfunction "28_28") (pintype "passive"))
    )
    (net (code "103") (name "unconnected-(J10-Pad30)") (class "Default")
      (node (ref "J10") (pin "30") (pinfunction "30_30") (pintype "passive"))
    )
    (net (code "104") (name "unconnected-(J10-Pad32)") (class "Default")
      (node (ref "J10") (pin "32") (pinfunction "32_32") (pintype "passive"))
    )
    (net (code "105") (name "unconnected-(J10-Pad37)") (class "Default")
      (node (ref "J10") (pin "37") (pinfunction "37_37") (pintype "passive"))
    )
    (net (code "106") (name "unconnected-(J10-Pad40)") (class "Default")
      (node (ref "J10") (pin "40") (pinfunction "40_40") (pintype "passive"))
    )
    (net (code "107") (name "unconnected-(J10-Pad41)") (class "Default")
      (node (ref "J10") (pin "41") (pinfunction "41_41") (pintype "passive"))
    )
    (net (code "108") (name "unconnected-(J10-Pad42)") (class "Default")
      (node (ref "J10") (pin "42") (pinfunction "42_42") (pintype "passive"))
    )
    (net (code "109") (name "unconnected-(J10-Pad43)") (class "Default")
      (node (ref "J10") (pin "43") (pinfunction "43_43") (pintype "passive"))
    )
    (net (code "110") (name "unconnected-(J10-Pad44)") (class "Default")
      (node (ref "J10") (pin "44") (pinfunction "44_44") (pintype "passive"))
    )
    (net (code "111") (name "unconnected-(J10-Pad57)") (class "Default")
      (node (ref "J10") (pin "57") (pinfunction "57_57") (pintype "passive"))
    )
    (net (code "112") (name "unconnected-(J10-Pad58)") (class "Default")
      (node (ref "J10") (pin "58") (pinfunction "58_58") (pintype "passive"))
    )
    (net (code "113") (name "unconnected-(J10-Pad60)") (class "Default")
      (node (ref "J10") (pin "60") (pinfunction "60_60") (pintype "passive"))
    )
    (net (code "114") (name "unconnected-(J10-Pad61)") (class "Default")
      (node (ref "J10") (pin "61") (pinfunction "61_61") (pintype "passive"))
    )
    (net (code "115") (name "unconnected-(J10-Pad62)") (class "Default")
      (node (ref "J10") (pin "62") (pinfunction "62_62") (pintype "passive"))
    )
    (net (code "116") (name "unconnected-(J10-Pad63)") (class "Default")
      (node (ref "J10") (pin "63") (pinfunction "63_63") (pintype "passive"))
    )
    (net (code "117") (name "unconnected-(J10-Pad64)") (class "Default")
      (node (ref "J10") (pin "64") (pinfunction "64_64") (pintype "passive"))
    )
    (net (code "118") (name "unconnected-(J10-Pad66)") (class "Default")
      (node (ref "J10") (pin "66") (pinfunction "66_66") (pintype "passive"))
    )
    (net (code "119") (name "unconnected-(J10-Pad67)") (class "Default")
      (node (ref "J10") (pin "67") (pinfunction "67_67") (pintype "passive"))
    )
    (net (code "120") (name "unconnected-(J10-Pad68)") (class "Default")
      (node (ref "J10") (pin "68") (pinfunction "68_68") (pintype "passive"))
    )
    (net (code "121") (name "unconnected-(J10-Pad69)") (class "Default")
      (node (ref "J10") (pin "69") (pinfunction "69_69") (pintype "passive"))
    )
    (net (code "122") (name "unconnected-(J10-Pad70)") (class "Default")
      (node (ref "J10") (pin "70") (pinfunction "70_70") (pintype "passive"))
    )
    (net (code "123") (name "unconnected-(J10-Pad71)") (class "Default")
      (node (ref "J10") (pin "71") (pinfunction "71_71") (pintype "passive"))
    )
    (net (code "124") (name "unconnected-(J10-Pad72)") (class "Default")
      (node (ref "J10") (pin "72") (pinfunction "72_72") (pintype "passive"))
    )
    (net (code "125") (name "unconnected-(J10-Pad73)") (class "Default")
      (node (ref "J10") (pin "73") (pinfunction "73_73") (pintype "passive"))
    )
    (net (code "126") (name "unconnected-(J10-Pad74)") (class "Default")
      (node (ref "J10") (pin "74") (pinfunction "74_74") (pintype "passive"))
    )
    (net (code "127") (name "unconnected-(J10-Pad76)") (class "Default")
      (node (ref "J10") (pin "76") (pinfunction "76_76") (pintype "passive"))
    )
    (net (code "128") (name "unconnected-(J10-Pad86)") (class "Default")
      (node (ref "J10") (pin "86") (pinfunction "86_86") (pintype "passive"))
    )
    (net (code "129") (name "unconnected-(J10-Pad88)") (class "Default")
      (node (ref "J10") (pin "88") (pinfunction "88_88") (pintype "passive"))
    )
    (net (code "130") (name "unconnected-(J10-Pad90)") (class "Default")
      (node (ref "J10") (pin "90") (pinfunction "90_90") (pintype "passive"))
    )
    (net (code "131") (name "unconnected-(J10-Pad92)") (class "Default")
      (node (ref "J10") (pin "92") (pinfunction "92_92") (pintype "passive"))
    )
    (net (code "132") (name "unconnected-(J10-Pad93)") (class "Default")
      (node (ref "J10") (pin "93") (pinfunction "93_93") (pintype "passive"))
    )
    (net (code "133") (name "unconnected-(J10-Pad95)") (class "Default")
      (node (ref "J10") (pin "95") (pinfunction "95_95") (pintype "passive"))
    )
    (net (code "134") (name "unconnected-(J10-Pad109)") (class "Default")
      (node (ref "J10") (pin "109") (pinfunction "109_109") (pintype "passive"))
    )
    (net (code "135") (name "unconnected-(J10-Pad113)") (class "Default")
      (node (ref "J10") (pin "113") (pinfunction "113_113") (pintype "passive"))
    )
    (net (code "136") (name "unconnected-(J10-Pad114)") (class "Default")
      (node (ref "J10") (pin "114") (pinfunction "114_114") (pintype "passive"))
    )
    (net (code "137") (name "unconnected-(J10-Pad115)") (class "Default")
      (node (ref "J10") (pin "115") (pinfunction "115_115") (pintype "passive"))
    )
    (net (code "138") (name "unconnected-(J10-Pad116)") (class "Default")
      (node (ref "J10") (pin "116") (pinfunction "116_116") (pintype "passive"))
    )
    (net (code "139") (name "unconnected-(J10-Pad117)") (class "Default")
      (node (ref "J10") (pin "117") (pinfunction "117_117") (pintype "passive"))
    )
    (net (code "140") (name "unconnected-(J10-Pad118)") (class "Default")
      (node (ref "J10") (pin "118") (pinfunction "118_118") (pintype "passive"))
    )
    (net (code "141") (name "unconnected-(J10-Pad120)") (class "Default")
      (node (ref "J10") (pin "120") (pinfunction "120_120") (pintype "passive"))
    )
  )
)
